# Stepper.net
KiCad netlist of a schematic drawn in Altium Designer
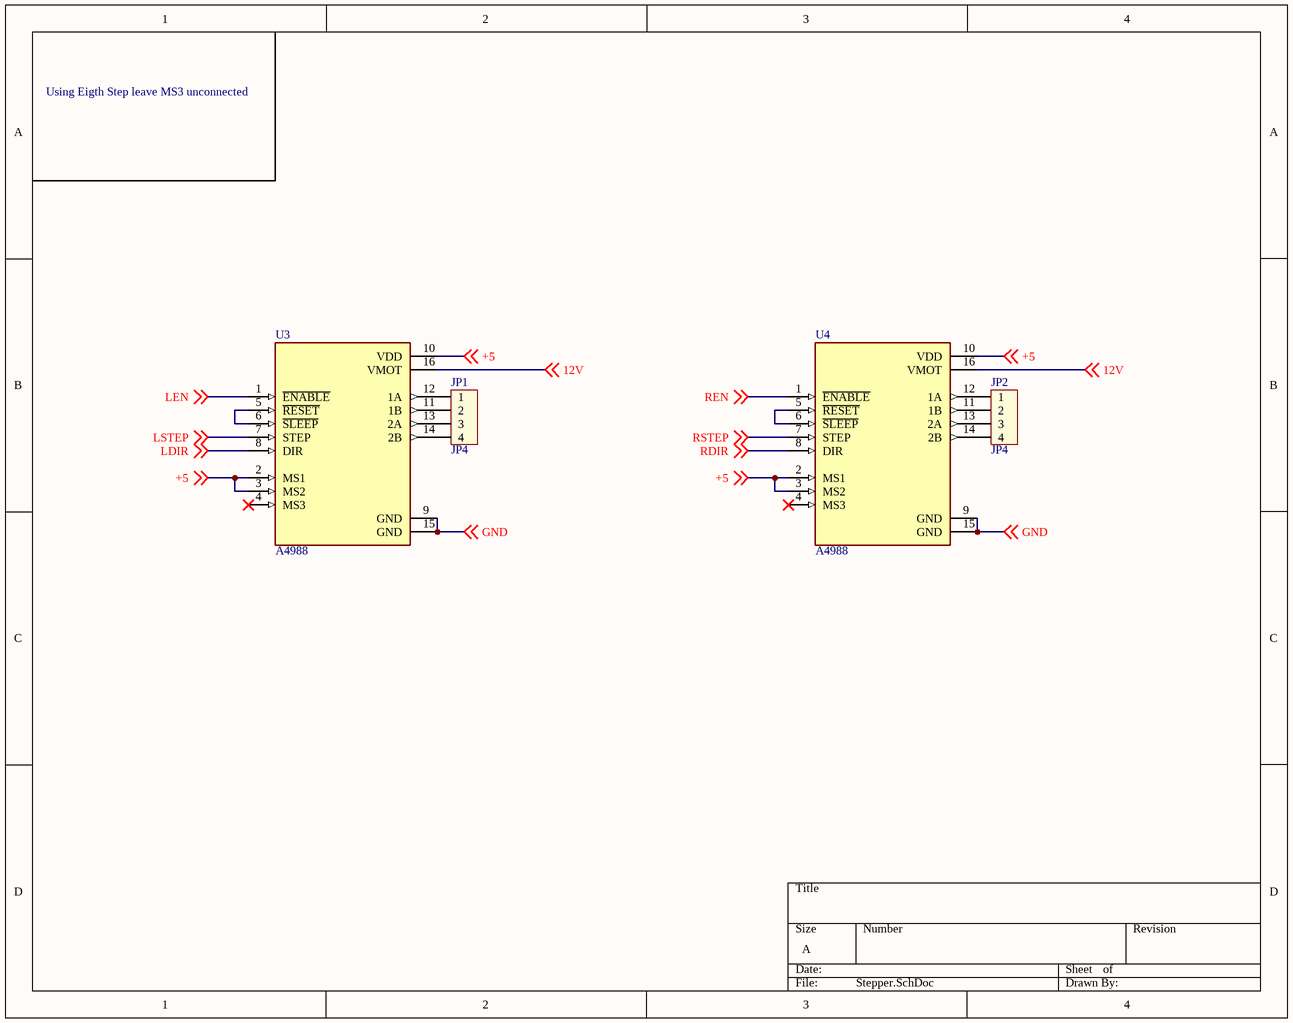
[diagram p0: Stepper.SchDoc]

(export (version "E")
  (design (tool "Eeschema 10.0.6"))
  (components
    (comp (ref "JP1")
      (value "JP4")
      (footprint "CON4")
      (description "Connector 4")
      (libsource (lib "Kiet") (part "Con4"))
    )
    (comp (ref "JP2")
      (value "JP4")
      (footprint "CON4")
      (description "Connector 4")
      (libsource (lib "Kiet") (part "Con4"))
    )
    (comp (ref "U3")
      (value "A4988")
      (footprint "MODULE_A4988_STEPPER_MOTOR_DRIVER_CARRIER")
      (description "Stepper motor controler; IC: A4988; 1A; Uin mot: 8Ã·35V")
      (fields (field (name "MP") "A4988_STEPPER_MOTOR_DRIVER_CARRIER"))
      (libsource (lib "A4988_STEPPER_MOTOR_DRIVER_CARRIER") (part "A4988_STEPPER_MOTOR_DRIVER_CARRIER"))
    )
    (comp (ref "U4")
      (value "A4988")
      (footprint "MODULE_A4988_STEPPER_MOTOR_DRIVER_CARRIER")
      (description "Stepper motor controler; IC: A4988; 1A; Uin mot: 8Ã·35V")
      (fields (field (name "MP") "A4988_STEPPER_MOTOR_DRIVER_CARRIER"))
      (libsource (lib "A4988_STEPPER_MOTOR_DRIVER_CARRIER") (part "A4988_STEPPER_MOTOR_DRIVER_CARRIER"))
    )
  )
  (nets
    (net (code "1") (name "+5") (class "Default")
      (node (ref "U3") (pin "10") (pinfunction "VDD_10") (pintype "power_in"))
      (node (ref "U3") (pin "2") (pinfunction "MS1_2") (pintype "input"))
      (node (ref "U3") (pin "3") (pinfunction "MS2_3") (pintype "input"))
      (node (ref "U4") (pin "10") (pinfunction "VDD_10") (pintype "power_in"))
      (node (ref "U4") (pin "2") (pinfunction "MS1_2") (pintype "input"))
      (node (ref "U4") (pin "3") (pinfunction "MS2_3") (pintype "input"))
    )
    (net (code "2") (name "12V") (class "Default")
      (node (ref "U3") (pin "16") (pinfunction "VMOT_16") (pintype "power_in"))
      (node (ref "U4") (pin "16") (pinfunction "VMOT_16") (pintype "power_in"))
    )
    (net (code "3") (name "GND") (class "Default")
      (node (ref "U3") (pin "15") (pinfunction "GND_15") (pintype "power_in"))
      (node (ref "U3") (pin "9") (pinfunction "GND_9") (pintype "power_in"))
      (node (ref "U4") (pin "15") (pinfunction "GND_15") (pintype "power_in"))
      (node (ref "U4") (pin "9") (pinfunction "GND_9") (pintype "power_in"))
    )
    (net (code "4") (name "LDIR") (class "Default")
      (node (ref "U3") (pin "8") (pinfunction "DIR_8") (pintype "input"))
    )
    (net (code "5") (name "LEN") (class "Default")
      (node (ref "U3") (pin "1") (pinfunction "~{ENABLE}_1") (pintype "input"))
    )
    (net (code "6") (name "LSTEP") (class "Default")
      (node (ref "U3") (pin "7") (pinfunction "STEP_7") (pintype "input"))
    )
    (net (code "7") (name "Net-(U3-1A)") (class "Default")
      (node (ref "JP1") (pin "1") (pinfunction "1_1") (pintype "passive"))
      (node (ref "U3") (pin "12") (pinfunction "1A_12") (pintype "output"))
    )
    (net (code "8") (name "Net-(U3-1B)") (class "Default")
      (node (ref "JP1") (pin "2") (pinfunction "2_2") (pintype "passive"))
      (node (ref "U3") (pin "11") (pinfunction "1B_11") (pintype "output"))
    )
    (net (code "9") (name "Net-(U3-2A)") (class "Default")
      (node (ref "JP1") (pin "3") (pinfunction "3_3") (pintype "passive"))
      (node (ref "U3") (pin "13") (pinfunction "2A_13") (pintype "output"))
    )
    (net (code "10") (name "Net-(U3-2B)") (class "Default")
      (node (ref "JP1") (pin "4") (pinfunction "4_4") (pintype "passive"))
      (node (ref "U3") (pin "14") (pinfunction "2B_14") (pintype "output"))
    )
    (net (code "11") (name "Net-(U3-~{RESET})") (class "Default")
      (node (ref "U3") (pin "5") (pinfunction "~{RESET}_5") (pintype "input"))
      (node (ref "U3") (pin "6") (pinfunction "~{SLEEP}_6") (pintype "input"))
    )
    (net (code "12") (name "Net-(U4-1A)") (class "Default")
      (node (ref "JP2") (pin "1") (pinfunction "1_1") (pintype "passive"))
      (node (ref "U4") (pin "12") (pinfunction "1A_12") (pintype "output"))
    )
    (net (code "13") (name "Net-(U4-1B)") (class "Default")
      (node (ref "JP2") (pin "2") (pinfunction "2_2") (pintype "passive"))
      (node (ref "U4") (pin "11") (pinfunction "1B_11") (pintype "output"))
    )
    (net (code "14") (name "Net-(U4-2A)") (class "Default")
      (node (ref "JP2") (pin "3") (pinfunction "3_3") (pintype "passive"))
      (node (ref "U4") (pin "13") (pinfunction "2A_13") (pintype "output"))
    )
    (net (code "15") (name "Net-(U4-2B)") (class "Default")
      (node (ref "JP2") (pin "4") (pinfunction "4_4") (pintype "passive"))
      (node (ref "U4") (pin "14") (pinfunction "2B_14") (pintype "output"))
    )
    (net (code "16") (name "Net-(U4-~{RESET})") (class "Default")
      (node (ref "U4") (pin "5") (pinfunction "~{RESET}_5") (pintype "input"))
      (node (ref "U4") (pin "6") (pinfunction "~{SLEEP}_6") (pintype "input"))
    )
    (net (code "17") (name "RDIR") (class "Default")
      (node (ref "U4") (pin "8") (pinfunction "DIR_8") (pintype "input"))
    )
    (net (code "18") (name "REN") (class "Default")
      (node (ref "U4") (pin "1") (pinfunction "~{ENABLE}_1") (pintype "input"))
    )
    (net (code "19") (name "RSTEP") (class "Default")
      (node (ref "U4") (pin "7") (pinfunction "STEP_7") (pintype "input"))
    )
    (net (code "20") (name "unconnected-(U3-MS3-Pad4)") (class "Default")
      (node (ref "U3") (pin "4") (pinfunction "MS3_4") (pintype "input+no_connect"))
    )
    (net (code "21") (name "unconnected-(U4-MS3-Pad4)") (class "Default")
      (node (ref "U4") (pin "4") (pinfunction "MS3_4") (pintype "input+no_connect"))
    )
  )
)
